# c4.net
KiCad netlist of a schematic drawn in EasyEDA Pro
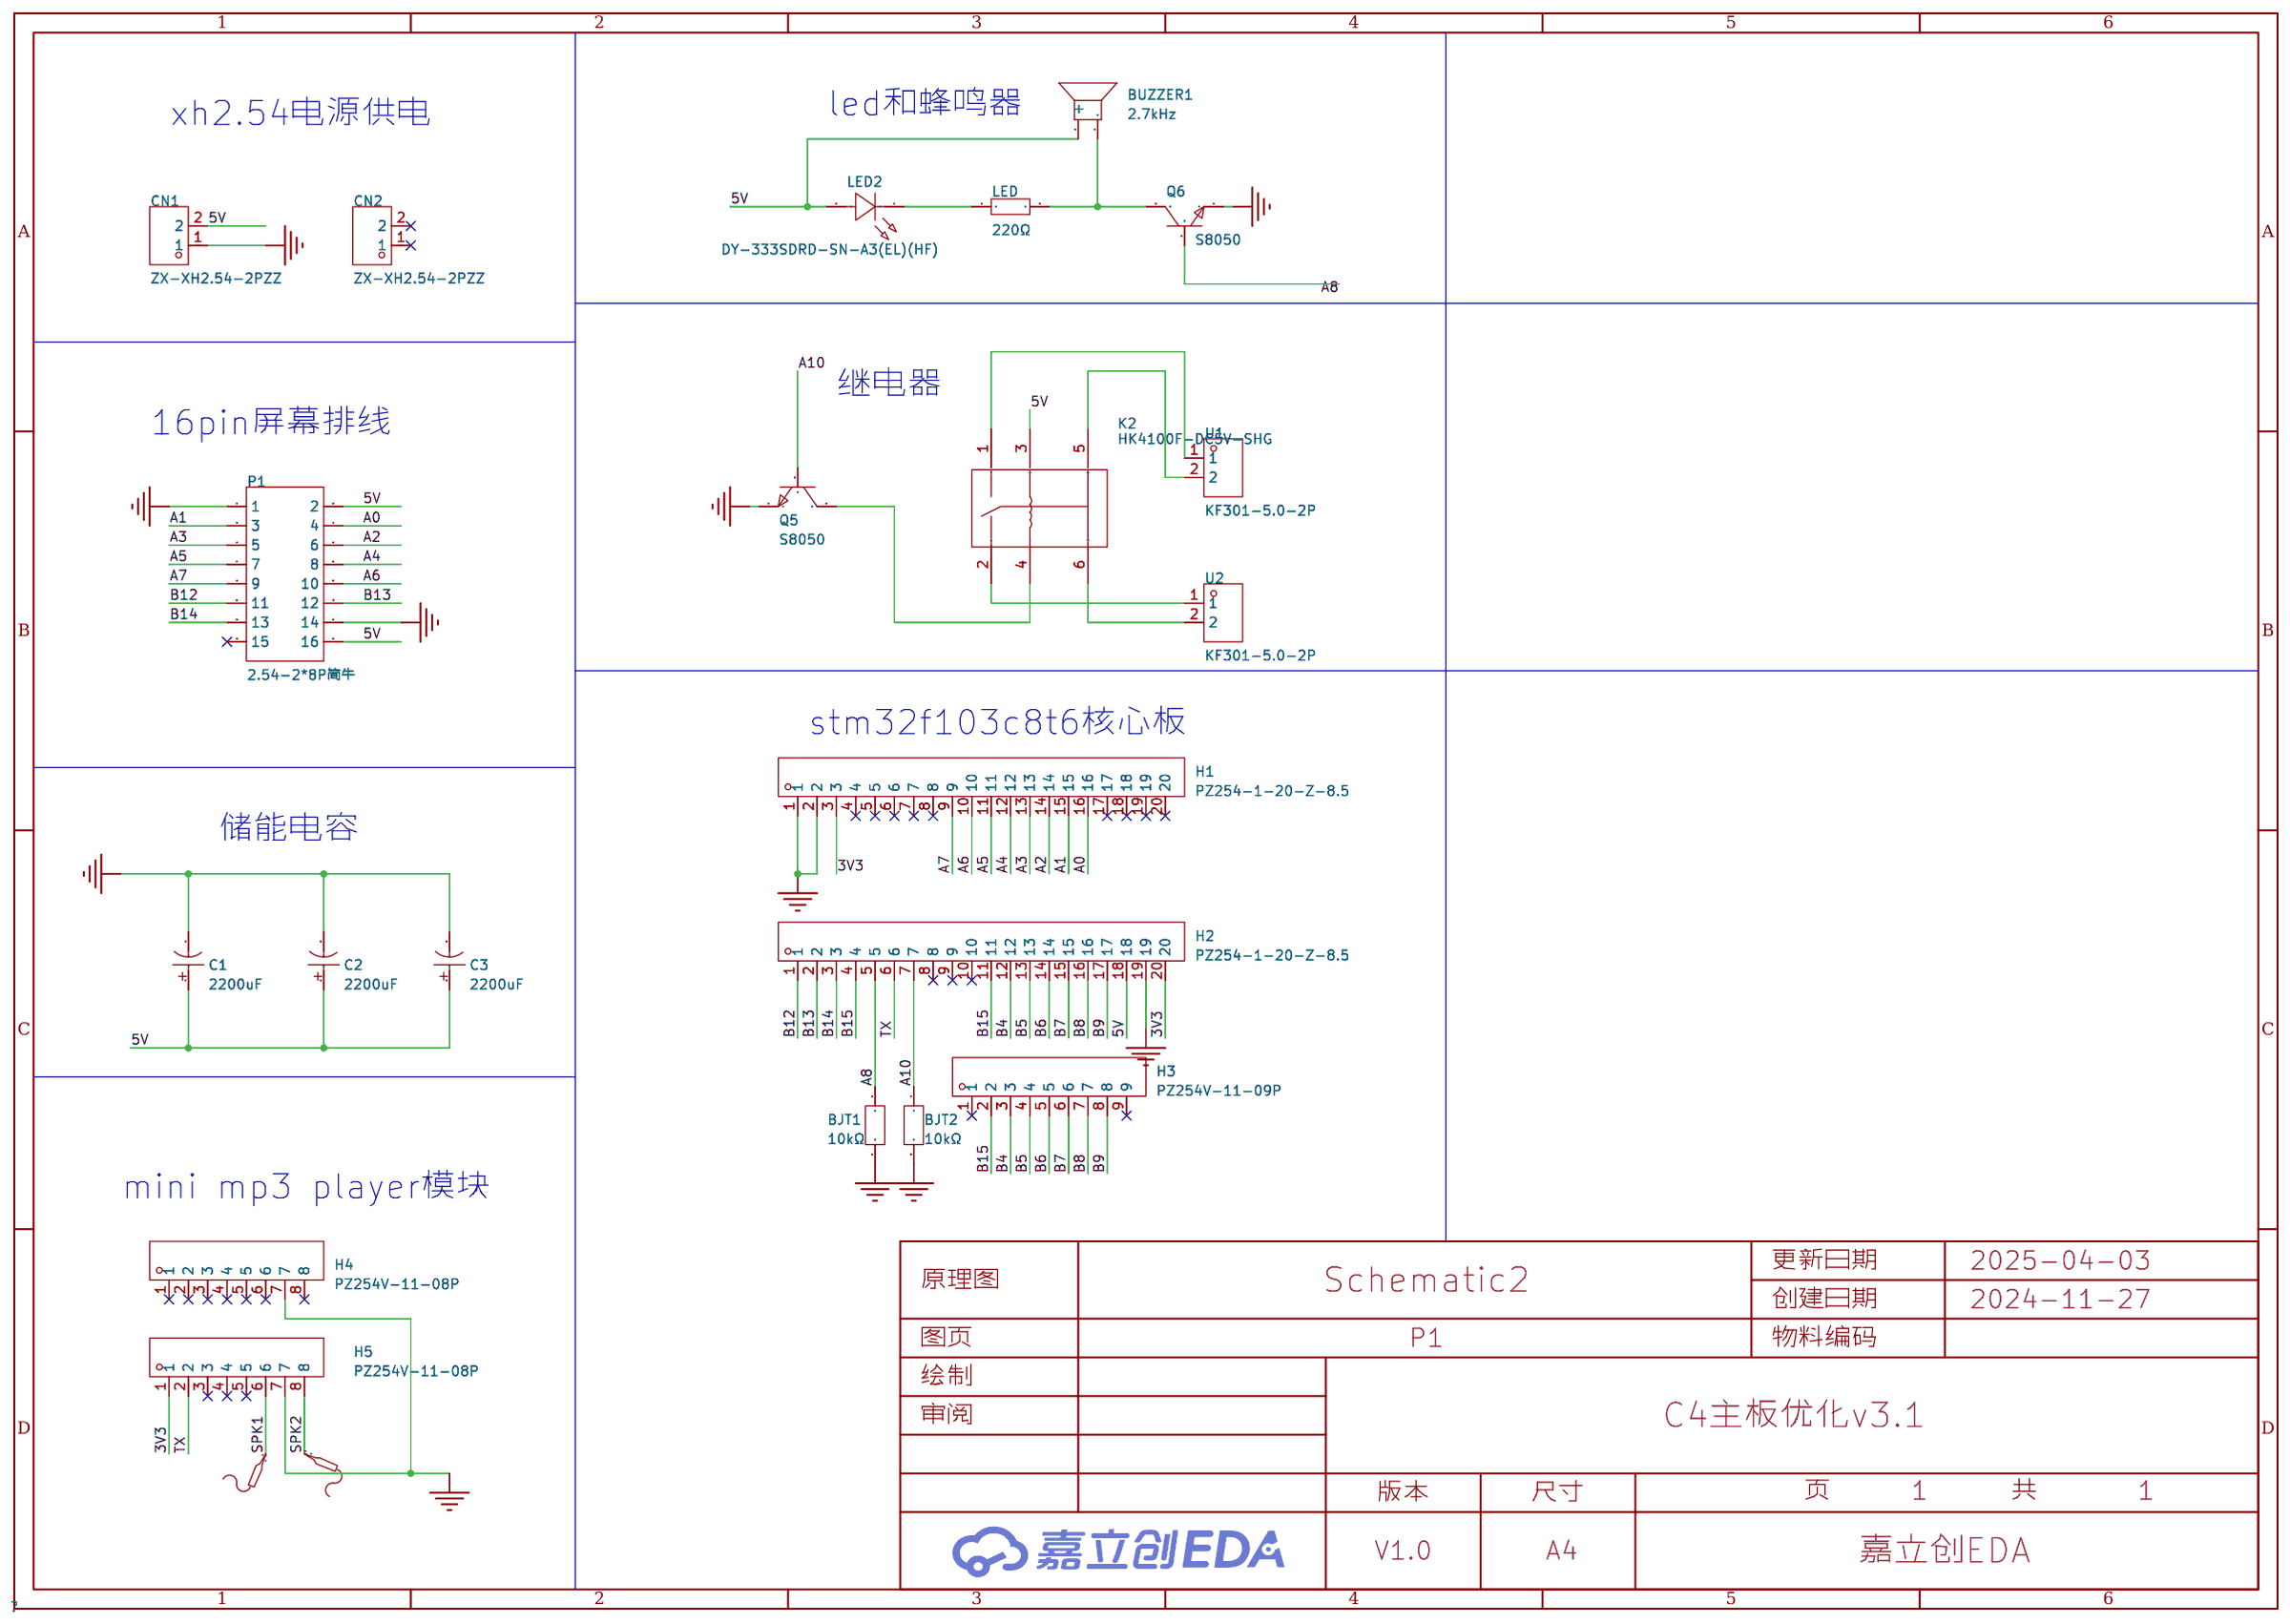
[diagram p0: schematic sheet]

(export (version "E")
  (design (tool "Eeschema 10.0.6"))
  (components
    (comp (ref "BJT1")
      (value "10kΩ")
      (footprint "easyedapro:RES-TH_BD2.7-L6.2-P10.20-D0.4")
      (description "电阻类型:金属膜电阻;阻值:10kΩ;精度:±1%;功率:250mW;温度系数:±100ppm/°C;")
      (fields (field (name "Manufacturer Part") "MF1/4W-10K±1%-ST52") (field (name "Manufacturer") "VO(翔胜)"))
      (libsource (lib "easyedapro") (part "MF1/4W-10K±1%-ST52"))
    )
    (comp (ref "BJT2")
      (value "10kΩ")
      (footprint "easyedapro:RES-TH_BD2.7-L6.2-P10.20-D0.4")
      (description "电阻类型:金属膜电阻;阻值:10kΩ;精度:±1%;功率:250mW;温度系数:±100ppm/°C;")
      (fields (field (name "Manufacturer Part") "MF1/4W-10K±1%-ST52") (field (name "Manufacturer") "VO(翔胜)"))
      (libsource (lib "easyedapro") (part "MF1/4W-10K±1%-ST52"))
    )
    (comp (ref "BUZZER1")
      (value "2.7kHz")
      (footprint "easyedapro:BUZ-TH_BD12.0-P7.60-D0.6-FD")
      (description "驱动方式:有源(内含驱动线路);构造类型:电磁式;频率:2.7kHz;声压(SPL):85dB@5V,10cm;")
      (fields (field (name "Manufacturer Part") "TMB12A05") (field (name "Manufacturer") "华能"))
      (libsource (lib "easyedapro") (part "TMB12A05"))
    )
    (comp (ref "C1")
      (value "2200uF")
      (footprint "easyedapro:CAP-TH_BD10.0-P5.00-D1.0-FD")
      (description "容值:2200uF;精度:±20%;额定电压:16V;纹波电流:-;等效串联电阻:-;")
      (fields
        (field (name "Manufacturer Part") "KM228M016G20RR0VH2FP0")
        (field (name "Manufacturer") "CX(承兴)")
      )
      (libsource (lib "easyedapro") (part "16V2200uf 10X20"))
    )
    (comp (ref "C2")
      (value "2200uF")
      (footprint "easyedapro:CAP-TH_BD10.0-P5.00-D1.0-FD")
      (description "容值:2200uF;精度:±20%;额定电压:16V;纹波电流:-;等效串联电阻:-;")
      (fields
        (field (name "Manufacturer Part") "KM228M016G20RR0VH2FP0")
        (field (name "Manufacturer") "CX(承兴)")
      )
      (libsource (lib "easyedapro") (part "16V2200uf 10X20"))
    )
    (comp (ref "C3")
      (value "2200uF")
      (footprint "easyedapro:CAP-TH_BD10.0-P5.00-D1.0-FD")
      (description "容值:2200uF;精度:±20%;额定电压:16V;纹波电流:-;等效串联电阻:-;")
      (fields
        (field (name "Manufacturer Part") "KM228M016G20RR0VH2FP0")
        (field (name "Manufacturer") "CX(承兴)")
      )
      (libsource (lib "easyedapro") (part "16V2200uf 10X20"))
    )
    (comp (ref "CN1")
      (value "ZX-XH2.54-2PZZ")
      (footprint "easyedapro:CONN-TH_2P-P2.50_HX25003-2A")
      (fields (field (name "Manufacturer") "Megastar(兆星)"))
      (libsource (lib "easyedapro") (part "ZX-XH2.54-2PZZ"))
    )
    (comp (ref "CN2")
      (value "ZX-XH2.54-2PZZ")
      (footprint "easyedapro:CONN-TH_2P-P2.50_HX25003-2A")
      (fields (field (name "Manufacturer") "Megastar(兆星)"))
      (libsource (lib "easyedapro") (part "ZX-XH2.54-2PZZ"))
    )
    (comp (ref "H1")
      (value "PZ254-1-20-Z-8.5")
      (footprint "easyedapro:HDR-TH_20P-P2.54-V-M")
      (fields (field (name "Manufacturer") "HCTL(华灿天禄)"))
      (libsource (lib "easyedapro") (part "PZ254-1-20-Z-8.5"))
    )
    (comp (ref "H2")
      (value "PZ254-1-20-Z-8.5")
      (footprint "easyedapro:HDR-TH_20P-P2.54-V-M")
      (fields (field (name "Manufacturer") "HCTL(华灿天禄)"))
      (libsource (lib "easyedapro") (part "PZ254-1-20-Z-8.5"))
    )
    (comp (ref "H3")
      (value "PZ254V-11-09P")
      (footprint "easyedapro:HDR-TH_9P-P2.54-V-M")
      (fields (field (name "Manufacturer") "XFCN(兴飞)"))
      (libsource (lib "easyedapro") (part "PZ254V-11-09P"))
    )
    (comp (ref "H4")
      (value "PZ254V-11-08P")
      (footprint "easyedapro:HDR-TH_8P-P2.54-V-M")
      (fields (field (name "Manufacturer") "XFCN(兴飞)"))
      (libsource (lib "easyedapro") (part "PZ254V-11-08P"))
    )
    (comp (ref "H5")
      (value "PZ254V-11-08P")
      (footprint "easyedapro:HDR-TH_8P-P2.54-V-M")
      (fields (field (name "Manufacturer") "XFCN(兴飞)"))
      (libsource (lib "easyedapro") (part "PZ254V-11-08P"))
    )
    (comp (ref "K2")
      (value "HK4100F-DC5V-SHG")
      (footprint "easyedapro:RELAY-TH_HK4100F-DC5V-SHG")
      (description "线圈电压:-;触点形式:-;触点容量(电阻负载):-;最大切换电压:-;最大切换电流:-;")
      (fields (field (name "Manufacturer") "汇科"))
      (libsource (lib "easyedapro") (part "HK4100F-DC5V-SHG"))
    )
    (comp (ref "LED")
      (value "220Ω")
      (footprint "easyedapro:RES-TH_BD2.4-L6.3-P10.30-D0.6")
      (description "电阻类型:金属膜电阻;阻值:47Ω;精度:±5%;功率:250mW;")
      (fields (field (name "Manufacturer Part") "MFR-25JT-52-47R") (field (name "Manufacturer") "YAGEO(国巨)"))
      (libsource (lib "easyedapro") (part "MFR-25JT-52-47R"))
    )
    (comp (ref "LED2")
      (value "DY-333SDRD-SN-A3(EL)(HF)")
      (footprint "easyedapro:LED-TH_BD5.9-P2.54-RD")
      (fields (field (name "Manufacturer") "TONYU(东裕)"))
      (libsource (lib "easyedapro") (part "DY-333SDRD-SN-A3(EL)(HF)"))
    )
    (comp (ref "P1")
      (value "2.54-2*8P简牛")
      (footprint "easyedapro:IDC-TH_16P-P2.54_C3406")
      (description "连接器类型:简牛座;间距:2.54mm;结构:2x8P;封装形式:直插;行距:2.54mm;排数:2;每排PIN数:8;触头材质:-;触头镀层:-;")
      (fields (field (name "Manufacturer") "BOOMELE(博穆精密)"))
      (libsource (lib "easyedapro") (part "HDR-IDC-2.54-2X8P"))
    )
    (comp (ref "Q5")
      (value "S8050")
      (footprint "easyedapro:TO-92-3_L4.5-W3.5-P1.27-L")
      (description "晶体管类型:NPN;集电极电流(Ic):500mA;集射极击穿电压(Vceo):25V;功率(Pd):625mW;直流电流增益(hFE@Ic,Vce):160@50mA,1V;")
      (fields (field (name "Manufacturer") "JSMSEMI(杰盛微)"))
      (libsource (lib "easyedapro") (part "S8050_C2931492"))
    )
    (comp (ref "Q6")
      (value "S8050")
      (footprint "easyedapro:TO-92-3_L4.5-W3.5-P1.27-L")
      (description "晶体管类型:NPN;集电极电流(Ic):500mA;集射极击穿电压(Vceo):25V;功率(Pd):625mW;直流电流增益(hFE@Ic,Vce):160@50mA,1V;")
      (fields (field (name "Manufacturer") "JSMSEMI(杰盛微)"))
      (libsource (lib "easyedapro") (part "S8050_C2931492"))
    )
    (comp (ref "SPK1")
      (value "~")
      (footprint "easyedapro:Test-Point-0.5mm")
      (description "Test Point 测试点")
      (libsource (lib "easyedapro") (part "Test-Point"))
    )
    (comp (ref "SPK2")
      (value "~")
      (footprint "easyedapro:Test-Point-0.5mm")
      (description "Test Point 测试点")
      (libsource (lib "easyedapro") (part "Test-Point"))
    )
    (comp (ref "U1")
      (value "KF301-5.0-2P")
      (footprint "easyedapro:CONN-TH_P5.00_KF301-5.0-2P")
      (fields (field (name "Manufacturer") "KEFA(科发)"))
      (libsource (lib "easyedapro") (part "KF301-5.0-2P"))
    )
    (comp (ref "U2")
      (value "KF301-5.0-2P")
      (footprint "easyedapro:CONN-TH_P5.00_KF301-5.0-2P")
      (fields (field (name "Manufacturer") "KEFA(科发)"))
      (libsource (lib "easyedapro") (part "KF301-5.0-2P"))
    )
  )
  (nets
    (net (code "1") (name "/3V3") (class "Default")
      (node (ref "H1") (pin "3") (pinfunction "3_3") (pintype "unspecified"))
      (node (ref "H2") (pin "20") (pinfunction "20_20") (pintype "unspecified"))
      (node (ref "H5") (pin "1") (pinfunction "1_1") (pintype "unspecified"))
    )
    (net (code "2") (name "/5V") (class "Default")
      (node (ref "BUZZER1") (pin "1") (pinfunction "+_1") (pintype "unspecified"))
      (node (ref "C1") (pin "1") (pinfunction "1_1") (pintype "input"))
      (node (ref "C2") (pin "1") (pinfunction "1_1") (pintype "input"))
      (node (ref "C3") (pin "1") (pinfunction "1_1") (pintype "input"))
      (node (ref "CN1") (pin "2") (pinfunction "2_2") (pintype "unspecified"))
      (node (ref "H2") (pin "18") (pinfunction "18_18") (pintype "unspecified"))
      (node (ref "K2") (pin "3") (pinfunction "3_3") (pintype "unspecified"))
      (node (ref "LED2") (pin "2") (pinfunction "A_2") (pintype "unspecified"))
      (node (ref "P1") (pin "16") (pinfunction "16_16") (pintype "unspecified"))
      (node (ref "P1") (pin "2") (pinfunction "2_2") (pintype "unspecified"))
    )
    (net (code "3") (name "/A0") (class "Default")
      (node (ref "H1") (pin "16") (pinfunction "16_16") (pintype "unspecified"))
      (node (ref "P1") (pin "4") (pinfunction "4_4") (pintype "unspecified"))
    )
    (net (code "4") (name "/A1") (class "Default")
      (node (ref "H1") (pin "15") (pinfunction "15_15") (pintype "unspecified"))
      (node (ref "P1") (pin "3") (pinfunction "3_3") (pintype "unspecified"))
    )
    (net (code "5") (name "/A2") (class "Default")
      (node (ref "H1") (pin "14") (pinfunction "14_14") (pintype "unspecified"))
      (node (ref "P1") (pin "6") (pinfunction "6_6") (pintype "unspecified"))
    )
    (net (code "6") (name "/A3") (class "Default")
      (node (ref "H1") (pin "13") (pinfunction "13_13") (pintype "unspecified"))
      (node (ref "P1") (pin "5") (pinfunction "5_5") (pintype "unspecified"))
    )
    (net (code "7") (name "/A4") (class "Default")
      (node (ref "H1") (pin "12") (pinfunction "12_12") (pintype "unspecified"))
      (node (ref "P1") (pin "8") (pinfunction "8_8") (pintype "unspecified"))
    )
    (net (code "8") (name "/A5") (class "Default")
      (node (ref "H1") (pin "11") (pinfunction "11_11") (pintype "unspecified"))
      (node (ref "P1") (pin "7") (pinfunction "7_7") (pintype "unspecified"))
    )
    (net (code "9") (name "/A6") (class "Default")
      (node (ref "H1") (pin "10") (pinfunction "10_10") (pintype "unspecified"))
      (node (ref "P1") (pin "10") (pinfunction "10_10") (pintype "unspecified"))
    )
    (net (code "10") (name "/A7") (class "Default")
      (node (ref "H1") (pin "9") (pinfunction "9_9") (pintype "unspecified"))
      (node (ref "P1") (pin "9") (pinfunction "9_9") (pintype "unspecified"))
    )
    (net (code "11") (name "/A8") (class "Default")
      (node (ref "BJT1") (pin "1") (pinfunction "1_1") (pintype "unspecified"))
      (node (ref "H2") (pin "5") (pinfunction "5_5") (pintype "unspecified"))
      (node (ref "Q6") (pin "2") (pinfunction "B_2") (pintype "unspecified"))
    )
    (net (code "12") (name "/A10") (class "Default")
      (node (ref "BJT2") (pin "1") (pinfunction "1_1") (pintype "unspecified"))
      (node (ref "H2") (pin "7") (pinfunction "7_7") (pintype "unspecified"))
      (node (ref "Q5") (pin "2") (pinfunction "B_2") (pintype "unspecified"))
    )
    (net (code "13") (name "/B4") (class "Default")
      (node (ref "H2") (pin "12") (pinfunction "12_12") (pintype "unspecified"))
      (node (ref "H3") (pin "3") (pinfunction "3_3") (pintype "unspecified"))
    )
    (net (code "14") (name "/B5") (class "Default")
      (node (ref "H2") (pin "13") (pinfunction "13_13") (pintype "unspecified"))
      (node (ref "H3") (pin "4") (pinfunction "4_4") (pintype "unspecified"))
    )
    (net (code "15") (name "/B6") (class "Default")
      (node (ref "H2") (pin "14") (pinfunction "14_14") (pintype "unspecified"))
      (node (ref "H3") (pin "5") (pinfunction "5_5") (pintype "unspecified"))
    )
    (net (code "16") (name "/B7") (class "Default")
      (node (ref "H2") (pin "15") (pinfunction "15_15") (pintype "unspecified"))
      (node (ref "H3") (pin "6") (pinfunction "6_6") (pintype "unspecified"))
    )
    (net (code "17") (name "/B8") (class "Default")
      (node (ref "H2") (pin "16") (pinfunction "16_16") (pintype "unspecified"))
      (node (ref "H3") (pin "7") (pinfunction "7_7") (pintype "unspecified"))
    )
    (net (code "18") (name "/B9") (class "Default")
      (node (ref "H2") (pin "17") (pinfunction "17_17") (pintype "unspecified"))
      (node (ref "H3") (pin "8") (pinfunction "8_8") (pintype "unspecified"))
    )
    (net (code "19") (name "/B12") (class "Default")
      (node (ref "H2") (pin "1") (pinfunction "1_1") (pintype "unspecified"))
      (node (ref "P1") (pin "11") (pinfunction "11_11") (pintype "unspecified"))
    )
    (net (code "20") (name "/B13") (class "Default")
      (node (ref "H2") (pin "2") (pinfunction "2_2") (pintype "unspecified"))
      (node (ref "P1") (pin "12") (pinfunction "12_12") (pintype "unspecified"))
    )
    (net (code "21") (name "/B14") (class "Default")
      (node (ref "H2") (pin "3") (pinfunction "3_3") (pintype "unspecified"))
      (node (ref "P1") (pin "13") (pinfunction "13_13") (pintype "unspecified"))
    )
    (net (code "22") (name "/B15") (class "Default")
      (node (ref "H2") (pin "11") (pinfunction "11_11") (pintype "unspecified"))
      (node (ref "H2") (pin "4") (pinfunction "4_4") (pintype "unspecified"))
      (node (ref "H3") (pin "2") (pinfunction "2_2") (pintype "unspecified"))
    )
    (net (code "23") (name "/SPK1") (class "Default")
      (node (ref "H5") (pin "6") (pinfunction "6_6") (pintype "unspecified"))
      (node (ref "SPK1") (pin "1") (pinfunction "1_1") (pintype "input"))
    )
    (net (code "24") (name "/SPK2") (class "Default")
      (node (ref "H5") (pin "8") (pinfunction "8_8") (pintype "unspecified"))
      (node (ref "SPK2") (pin "1") (pinfunction "1_1") (pintype "input"))
    )
    (net (code "25") (name "/TX") (class "Default")
      (node (ref "H2") (pin "6") (pinfunction "6_6") (pintype "unspecified"))
      (node (ref "H5") (pin "2") (pinfunction "2_2") (pintype "unspecified"))
    )
    (net (code "26") (name "GND") (class "Default")
      (node (ref "BJT1") (pin "2") (pinfunction "2_2") (pintype "unspecified"))
      (node (ref "BJT2") (pin "2") (pinfunction "2_2") (pintype "unspecified"))
      (node (ref "C1") (pin "2") (pinfunction "2_2") (pintype "input"))
      (node (ref "C2") (pin "2") (pinfunction "2_2") (pintype "input"))
      (node (ref "C3") (pin "2") (pinfunction "2_2") (pintype "input"))
      (node (ref "CN1") (pin "1") (pinfunction "1_1") (pintype "unspecified"))
      (node (ref "H1") (pin "1") (pinfunction "1_1") (pintype "unspecified"))
      (node (ref "H1") (pin "2") (pinfunction "2_2") (pintype "unspecified"))
      (node (ref "H2") (pin "19") (pinfunction "19_19") (pintype "unspecified"))
      (node (ref "H4") (pin "7") (pinfunction "7_7") (pintype "unspecified"))
      (node (ref "H5") (pin "7") (pinfunction "7_7") (pintype "unspecified"))
      (node (ref "P1") (pin "1") (pinfunction "1_1") (pintype "unspecified"))
      (node (ref "P1") (pin "14") (pinfunction "14_14") (pintype "unspecified"))
      (node (ref "Q5") (pin "1") (pinfunction "E_1") (pintype "unspecified"))
      (node (ref "Q6") (pin "1") (pinfunction "E_1") (pintype "unspecified"))
    )
    (net (code "27") (name "Net-(K2-Pad1)") (class "Default")
      (node (ref "K2") (pin "1") (pinfunction "1_1") (pintype "unspecified"))
      (node (ref "U1") (pin "1") (pinfunction "1_1") (pintype "unspecified"))
    )
    (net (code "28") (name "Net-(K2-Pad2)") (class "Default")
      (node (ref "K2") (pin "2") (pinfunction "2_2") (pintype "unspecified"))
      (node (ref "U2") (pin "1") (pinfunction "1_1") (pintype "unspecified"))
    )
    (net (code "29") (name "Net-(K2-Pad5)") (class "Default")
      (node (ref "K2") (pin "5") (pinfunction "5_5") (pintype "unspecified"))
      (node (ref "U1") (pin "2") (pinfunction "2_2") (pintype "unspecified"))
    )
    (net (code "30") (name "Net-(K2-Pad6)") (class "Default")
      (node (ref "K2") (pin "6") (pinfunction "6_6") (pintype "unspecified"))
      (node (ref "U2") (pin "2") (pinfunction "2_2") (pintype "unspecified"))
    )
    (net (code "31") (name "Net-(LED2-K)") (class "Default")
      (node (ref "LED") (pin "1") (pinfunction "1_1") (pintype "unspecified"))
      (node (ref "LED2") (pin "1") (pinfunction "K_1") (pintype "unspecified"))
    )
    (net (code "32") (name "Net-(Q5-C)") (class "Default")
      (node (ref "K2") (pin "4") (pinfunction "4_4") (pintype "unspecified"))
      (node (ref "Q5") (pin "3") (pinfunction "C_3") (pintype "unspecified"))
    )
    (net (code "33") (name "Net-(Q6-C)") (class "Default")
      (node (ref "BUZZER1") (pin "2") (pinfunction "2_2") (pintype "unspecified"))
      (node (ref "LED") (pin "2") (pinfunction "2_2") (pintype "unspecified"))
      (node (ref "Q6") (pin "3") (pinfunction "C_3") (pintype "unspecified"))
    )
    (net (code "34") (name "unconnected-(CN2-Pad1)") (class "Default")
      (node (ref "CN2") (pin "1") (pinfunction "1_1") (pintype "unspecified+no_connect"))
    )
    (net (code "35") (name "unconnected-(CN2-Pad2)") (class "Default")
      (node (ref "CN2") (pin "2") (pinfunction "2_2") (pintype "unspecified+no_connect"))
    )
    (net (code "36") (name "unconnected-(H1-Pad4)") (class "Default")
      (node (ref "H1") (pin "4") (pinfunction "4_4") (pintype "unspecified+no_connect"))
    )
    (net (code "37") (name "unconnected-(H1-Pad5)") (class "Default")
      (node (ref "H1") (pin "5") (pinfunction "5_5") (pintype "unspecified+no_connect"))
    )
    (net (code "38") (name "unconnected-(H1-Pad6)") (class "Default")
      (node (ref "H1") (pin "6") (pinfunction "6_6") (pintype "unspecified+no_connect"))
    )
    (net (code "39") (name "unconnected-(H1-Pad7)") (class "Default")
      (node (ref "H1") (pin "7") (pinfunction "7_7") (pintype "unspecified+no_connect"))
    )
    (net (code "40") (name "unconnected-(H1-Pad8)") (class "Default")
      (node (ref "H1") (pin "8") (pinfunction "8_8") (pintype "unspecified+no_connect"))
    )
    (net (code "41") (name "unconnected-(H1-Pad17)") (class "Default")
      (node (ref "H1") (pin "17") (pinfunction "17_17") (pintype "unspecified+no_connect"))
    )
    (net (code "42") (name "unconnected-(H1-Pad18)") (class "Default")
      (node (ref "H1") (pin "18") (pinfunction "18_18") (pintype "unspecified+no_connect"))
    )
    (net (code "43") (name "unconnected-(H1-Pad19)") (class "Default")
      (node (ref "H1") (pin "19") (pinfunction "19_19") (pintype "unspecified+no_connect"))
    )
    (net (code "44") (name "unconnected-(H1-Pad20)") (class "Default")
      (node (ref "H1") (pin "20") (pinfunction "20_20") (pintype "unspecified+no_connect"))
    )
    (net (code "45") (name "unconnected-(H2-Pad8)") (class "Default")
      (node (ref "H2") (pin "8") (pinfunction "8_8") (pintype "unspecified+no_connect"))
    )
    (net (code "46") (name "unconnected-(H2-Pad9)") (class "Default")
      (node (ref "H2") (pin "9") (pinfunction "9_9") (pintype "unspecified+no_connect"))
    )
    (net (code "47") (name "unconnected-(H2-Pad10)") (class "Default")
      (node (ref "H2") (pin "10") (pinfunction "10_10") (pintype "unspecified+no_connect"))
    )
    (net (code "48") (name "unconnected-(H3-Pad1)") (class "Default")
      (node (ref "H3") (pin "1") (pinfunction "1_1") (pintype "unspecified+no_connect"))
    )
    (net (code "49") (name "unconnected-(H3-Pad9)") (class "Default")
      (node (ref "H3") (pin "9") (pinfunction "9_9") (pintype "unspecified+no_connect"))
    )
    (net (code "50") (name "unconnected-(H4-Pad1)") (class "Default")
      (node (ref "H4") (pin "1") (pinfunction "1_1") (pintype "unspecified+no_connect"))
    )
    (net (code "51") (name "unconnected-(H4-Pad2)") (class "Default")
      (node (ref "H4") (pin "2") (pinfunction "2_2") (pintype "unspecified+no_connect"))
    )
    (net (code "52") (name "unconnected-(H4-Pad3)") (class "Default")
      (node (ref "H4") (pin "3") (pinfunction "3_3") (pintype "unspecified+no_connect"))
    )
    (net (code "53") (name "unconnected-(H4-Pad4)") (class "Default")
      (node (ref "H4") (pin "4") (pinfunction "4_4") (pintype "unspecified+no_connect"))
    )
    (net (code "54") (name "unconnected-(H4-Pad5)") (class "Default")
      (node (ref "H4") (pin "5") (pinfunction "5_5") (pintype "unspecified+no_connect"))
    )
    (net (code "55") (name "unconnected-(H4-Pad6)") (class "Default")
      (node (ref "H4") (pin "6") (pinfunction "6_6") (pintype "unspecified+no_connect"))
    )
    (net (code "56") (name "unconnected-(H4-Pad8)") (class "Default")
      (node (ref "H4") (pin "8") (pinfunction "8_8") (pintype "unspecified+no_connect"))
    )
    (net (code "57") (name "unconnected-(H5-Pad3)") (class "Default")
      (node (ref "H5") (pin "3") (pinfunction "3_3") (pintype "unspecified+no_connect"))
    )
    (net (code "58") (name "unconnected-(H5-Pad4)") (class "Default")
      (node (ref "H5") (pin "4") (pinfunction "4_4") (pintype "unspecified+no_connect"))
    )
    (net (code "59") (name "unconnected-(H5-Pad5)") (class "Default")
      (node (ref "H5") (pin "5") (pinfunction "5_5") (pintype "unspecified+no_connect"))
    )
    (net (code "60") (name "unconnected-(P1-Pad15)") (class "Default")
      (node (ref "P1") (pin "15") (pinfunction "15_15") (pintype "unspecified+no_connect"))
    )
  )
)
